# PlantSensorFoot.net
KiCad netlist of a schematic drawn in EAGLE
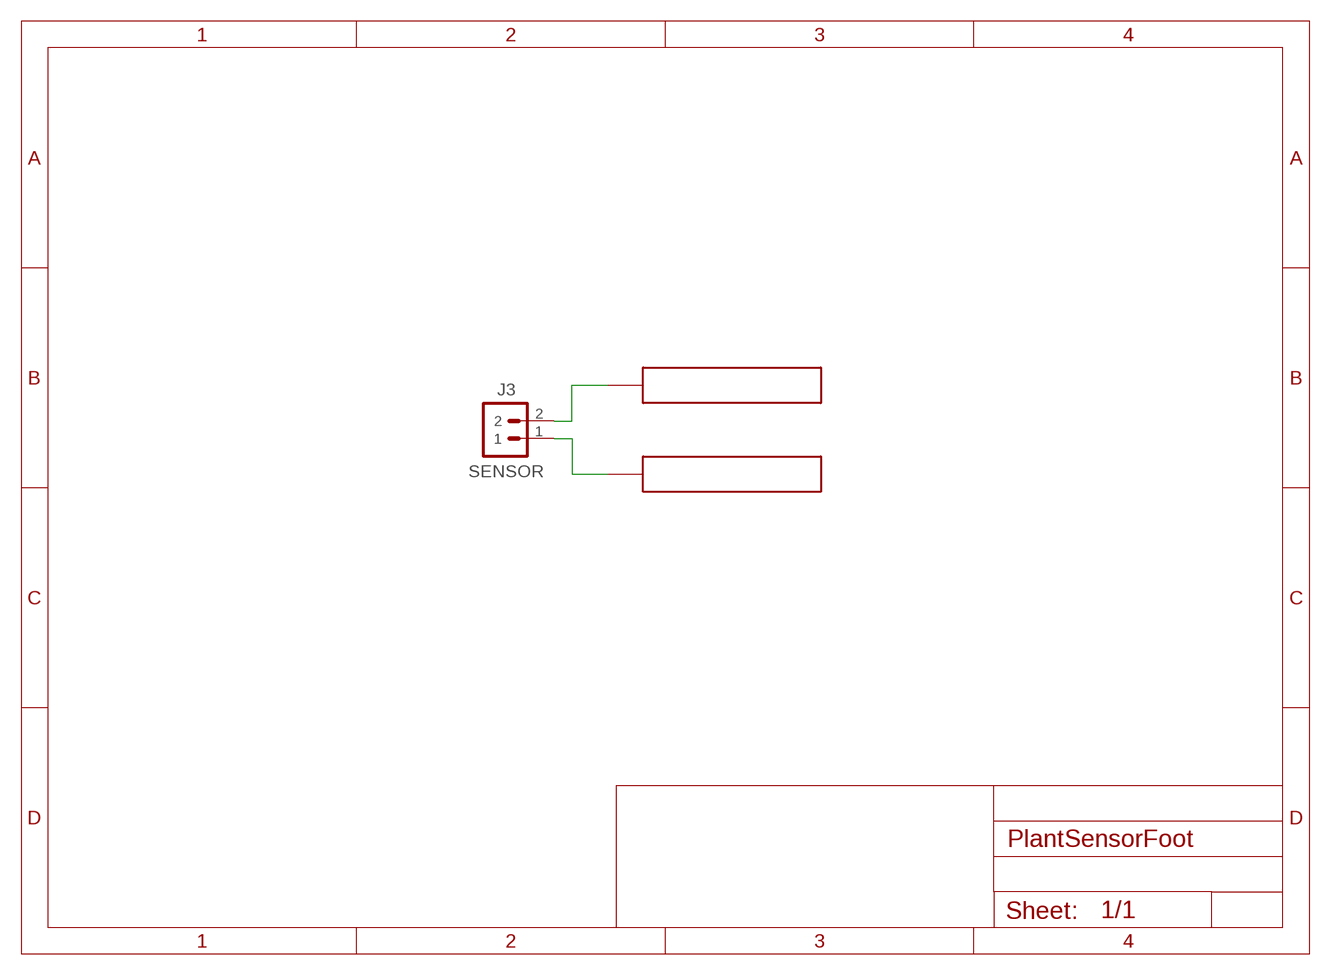
[diagram p0: schematic, sheet 1]

(export (version "E")
  (design (tool "Eeschema 10.0.6"))
  (components
    (comp (ref "CP1")
      (value "CAP_PAD_5X30")
      (footprint "eagle-import:CAP_PLATE_5X30")
      (libsource (lib "eagle-import") (part "CAP_PAD_5X30"))
    )
    (comp (ref "CP2")
      (value "CAP_PAD_5X30")
      (footprint "eagle-import:CAP_PLATE_5X30")
      (libsource (lib "eagle-import") (part "CAP_PAD_5X30"))
    )
    (comp (ref "J3")
      (value "SENSOR")
      (footprint "eagle-import:CON_PADS_2XWIRE")
      (libsource (lib "eagle-import") (part "CON_2X1WIREPADS"))
    )
  )
  (nets
    (net (code "1") (name "Net-(CP1-Pad1)") (class "Default")
      (node (ref "CP1") (pin "1") (pinfunction "1_1") (pintype "passive"))
      (node (ref "J3") (pin "2") (pinfunction "2_2") (pintype "passive"))
    )
    (net (code "2") (name "Net-(CP2-Pad1)") (class "Default")
      (node (ref "CP2") (pin "1") (pinfunction "1_1") (pintype "passive"))
      (node (ref "J3") (pin "1") (pinfunction "1_1") (pintype "passive"))
    )
  )
)
